# Rotary-Buttons.net
KiCad netlist of a schematic drawn in EAGLE
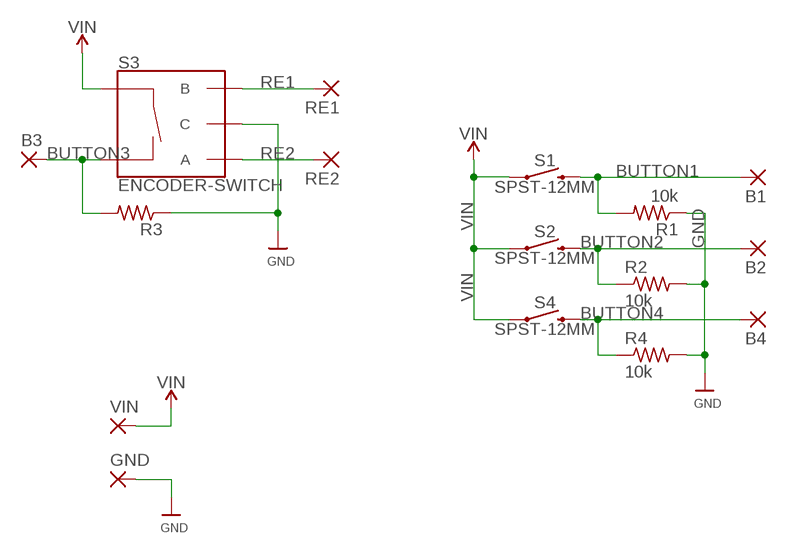
[diagram p0: schematic, sheet 1]

(export (version "E")
  (design (tool "Eeschema 10.0.6"))
  (components
    (comp (ref "B1")
      (value "SMD5")
      (footprint "eagle-import:SMD2,54-5,08")
      (libsource (lib "eagle-import") (part "SMD5"))
    )
    (comp (ref "B2")
      (value "SMD5")
      (footprint "eagle-import:SMD2,54-5,08")
      (libsource (lib "eagle-import") (part "SMD5"))
    )
    (comp (ref "B3")
      (value "SMD5")
      (footprint "eagle-import:SMD2,54-5,08")
      (libsource (lib "eagle-import") (part "SMD5"))
    )
    (comp (ref "B4")
      (value "SMD5")
      (footprint "eagle-import:SMD2,54-5,08")
      (libsource (lib "eagle-import") (part "SMD5"))
    )
    (comp (ref "GND")
      (value "SMD5")
      (footprint "eagle-import:SMD2,54-5,08")
      (libsource (lib "eagle-import") (part "SMD5"))
    )
    (comp (ref "R1")
      (value "10k")
      (footprint "eagle-import:R1206")
      (libsource (lib "eagle-import") (part "R-US_R1206"))
    )
    (comp (ref "R2")
      (value "10k")
      (footprint "eagle-import:R1206")
      (libsource (lib "eagle-import") (part "R-US_R1206"))
    )
    (comp (ref "R3")
      (value "R-US_R1206")
      (footprint "eagle-import:R1206")
      (libsource (lib "eagle-import") (part "R-US_R1206"))
    )
    (comp (ref "R4")
      (value "10k")
      (footprint "eagle-import:R1206")
      (libsource (lib "eagle-import") (part "R-US_R1206"))
    )
    (comp (ref "RE1")
      (value "SMD5")
      (footprint "eagle-import:SMD2,54-5,08")
      (libsource (lib "eagle-import") (part "SMD5"))
    )
    (comp (ref "RE2")
      (value "SMD5")
      (footprint "eagle-import:SMD2,54-5,08")
      (libsource (lib "eagle-import") (part "SMD5"))
    )
    (comp (ref "S1")
      (value "SPST-12MM")
      (footprint "eagle-import:TACTILE_SWITCH_PTH_12MM")
      (libsource (lib "eagle-import") (part "MOMENTARY-SWITCH-SPST-PTH-12MM"))
    )
    (comp (ref "S2")
      (value "SPST-12MM")
      (footprint "eagle-import:TACTILE_SWITCH_PTH_12MM")
      (libsource (lib "eagle-import") (part "MOMENTARY-SWITCH-SPST-PTH-12MM"))
    )
    (comp (ref "S3")
      (value "ENCODER-SWITCH")
      (footprint "eagle-import:ROTARY_ENC_PLAIN")
      (libsource (lib "eagle-import") (part "ENCODER-SWITCH"))
    )
    (comp (ref "S4")
      (value "SPST-12MM")
      (footprint "eagle-import:TACTILE_SWITCH_PTH_12MM")
      (libsource (lib "eagle-import") (part "MOMENTARY-SWITCH-SPST-PTH-12MM"))
    )
    (comp (ref "VIN")
      (value "SMD5")
      (footprint "eagle-import:SMD2,54-5,08")
      (libsource (lib "eagle-import") (part "SMD5"))
    )
  )
  (nets
    (net (code "1") (name "/BUTTON1") (class "Default")
      (node (ref "B1") (pin "1") (pinfunction "P_1") (pintype "passive"))
      (node (ref "R1") (pin "2") (pinfunction "2_2") (pintype "passive"))
      (node (ref "S1") (pin "3") (pinfunction "2_3") (pintype "passive"))
    )
    (net (code "2") (name "/BUTTON2") (class "Default")
      (node (ref "B2") (pin "1") (pinfunction "P_1") (pintype "passive"))
      (node (ref "R2") (pin "1") (pinfunction "1_1") (pintype "passive"))
      (node (ref "S2") (pin "3") (pinfunction "2_3") (pintype "passive"))
    )
    (net (code "3") (name "/BUTTON3") (class "Default")
      (node (ref "B3") (pin "1") (pinfunction "P_1") (pintype "passive"))
      (node (ref "R3") (pin "2") (pinfunction "2_2") (pintype "passive"))
      (node (ref "S3") (pin "SW-") (pinfunction "SW-_SW-") (pintype "bidirectional"))
    )
    (net (code "4") (name "/BUTTON4") (class "Default")
      (node (ref "B4") (pin "1") (pinfunction "P_1") (pintype "passive"))
      (node (ref "R4") (pin "1") (pinfunction "1_1") (pintype "passive"))
      (node (ref "S4") (pin "3") (pinfunction "2_3") (pintype "passive"))
    )
    (net (code "5") (name "/RE1") (class "Default")
      (node (ref "RE1") (pin "1") (pinfunction "P_1") (pintype "passive"))
      (node (ref "S3") (pin "B") (pinfunction "B_B") (pintype "bidirectional"))
    )
    (net (code "6") (name "/RE2") (class "Default")
      (node (ref "RE2") (pin "1") (pinfunction "P_1") (pintype "passive"))
      (node (ref "S3") (pin "A") (pinfunction "A_A") (pintype "bidirectional"))
    )
    (net (code "7") (name "GND") (class "Default")
      (node (ref "GND") (pin "1") (pinfunction "P_1") (pintype "passive"))
      (node (ref "R1") (pin "1") (pinfunction "1_1") (pintype "passive"))
      (node (ref "R2") (pin "2") (pinfunction "2_2") (pintype "passive"))
      (node (ref "R3") (pin "1") (pinfunction "1_1") (pintype "passive"))
      (node (ref "R4") (pin "2") (pinfunction "2_2") (pintype "passive"))
      (node (ref "S3") (pin "C") (pinfunction "C_C") (pintype "bidirectional"))
    )
    (net (code "8") (name "VIN") (class "Default")
      (node (ref "S1") (pin "1") (pinfunction "1_1") (pintype "passive"))
      (node (ref "S2") (pin "1") (pinfunction "1_1") (pintype "passive"))
      (node (ref "S3") (pin "SW+") (pinfunction "SW+_SW+") (pintype "bidirectional"))
      (node (ref "S4") (pin "1") (pinfunction "1_1") (pintype "passive"))
      (node (ref "VIN") (pin "1") (pinfunction "P_1") (pintype "passive"))
    )
  )
)
